# Slave4.net
KiCad netlist of a schematic drawn in Altium Designer
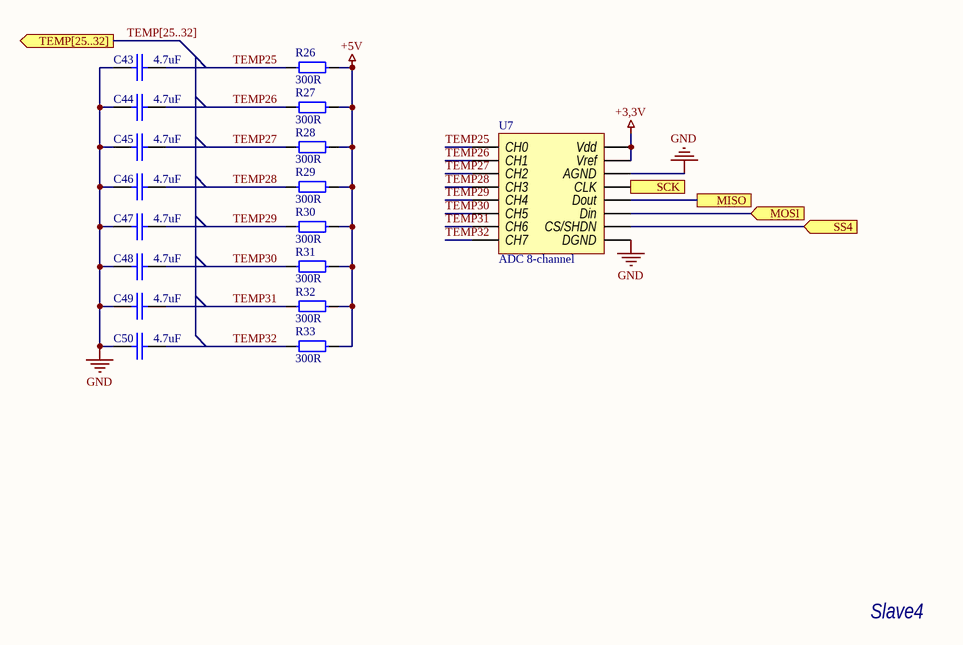
[diagram p0: Slave4.SchDoc]

(export (version "E")
  (design (tool "Eeschema 10.0.6"))
  (components
    (comp (ref "C43")
      (value "4.7uF")
      (footprint "0603 Capicator")
      (description "4.7uF X5R 25V 10% 0603")
      (fields
        (field (name "MANUFACTURER") "Murata Manufacturing")
        (field (name "PART NUMBER") "GRM188R61E475KE11D")
      )
      (libsource (lib "БУС") (part "Cap 4.7uF (0603)"))
    )
    (comp (ref "C44")
      (value "4.7uF")
      (footprint "0603 Capicator")
      (description "4.7uF X5R 25V 10% 0603")
      (fields
        (field (name "MANUFACTURER") "Murata Manufacturing")
        (field (name "PART NUMBER") "GRM188R61E475KE11D")
      )
      (libsource (lib "БУС") (part "Cap 4.7uF (0603)"))
    )
    (comp (ref "C45")
      (value "4.7uF")
      (footprint "0603 Capicator")
      (description "4.7uF X5R 25V 10% 0603")
      (fields
        (field (name "MANUFACTURER") "Murata Manufacturing")
        (field (name "PART NUMBER") "GRM188R61E475KE11D")
      )
      (libsource (lib "БУС") (part "Cap 4.7uF (0603)"))
    )
    (comp (ref "C46")
      (value "4.7uF")
      (footprint "0603 Capicator")
      (description "4.7uF X5R 25V 10% 0603")
      (fields
        (field (name "MANUFACTURER") "Murata Manufacturing")
        (field (name "PART NUMBER") "GRM188R61E475KE11D")
      )
      (libsource (lib "БУС") (part "Cap 4.7uF (0603)"))
    )
    (comp (ref "C47")
      (value "4.7uF")
      (footprint "0603 Capicator")
      (description "4.7uF X5R 25V 10% 0603")
      (fields
        (field (name "MANUFACTURER") "Murata Manufacturing")
        (field (name "PART NUMBER") "GRM188R61E475KE11D")
      )
      (libsource (lib "БУС") (part "Cap 4.7uF (0603)"))
    )
    (comp (ref "C48")
      (value "4.7uF")
      (footprint "0603 Capicator")
      (description "4.7uF X5R 25V 10% 0603")
      (fields
        (field (name "MANUFACTURER") "Murata Manufacturing")
        (field (name "PART NUMBER") "GRM188R61E475KE11D")
      )
      (libsource (lib "БУС") (part "Cap 4.7uF (0603)"))
    )
    (comp (ref "C49")
      (value "4.7uF")
      (footprint "0603 Capicator")
      (description "4.7uF X5R 25V 10% 0603")
      (fields
        (field (name "MANUFACTURER") "Murata Manufacturing")
        (field (name "PART NUMBER") "GRM188R61E475KE11D")
      )
      (libsource (lib "БУС") (part "Cap 4.7uF (0603)"))
    )
    (comp (ref "C50")
      (value "4.7uF")
      (footprint "0603 Capicator")
      (description "4.7uF X5R 25V 10% 0603")
      (fields
        (field (name "MANUFACTURER") "Murata Manufacturing")
        (field (name "PART NUMBER") "GRM188R61E475KE11D")
      )
      (libsource (lib "БУС") (part "Cap 4.7uF (0603)"))
    )
    (comp (ref "R26")
      (value "300R")
      (footprint "0603 Resistor")
      (description "0.1W 0603 300R, 1%")
      (fields (field (name "PART NUMBER") "RC0603FR-07360RL") (field (name "MANUFACTURER") "Taiwan"))
      (libsource (lib "БУС") (part "Res 300R (0603)"))
    )
    (comp (ref "R27")
      (value "300R")
      (footprint "0603 Resistor")
      (description "0.1W 0603 300R, 1%")
      (fields (field (name "PART NUMBER") "RC0603FR-07360RL") (field (name "MANUFACTURER") "Taiwan"))
      (libsource (lib "БУС") (part "Res 300R (0603)"))
    )
    (comp (ref "R28")
      (value "300R")
      (footprint "0603 Resistor")
      (description "0.1W 0603 300R, 1%")
      (fields (field (name "PART NUMBER") "RC0603FR-07360RL") (field (name "MANUFACTURER") "Taiwan"))
      (libsource (lib "БУС") (part "Res 300R (0603)"))
    )
    (comp (ref "R29")
      (value "300R")
      (footprint "0603 Resistor")
      (description "0.1W 0603 300R, 1%")
      (fields (field (name "PART NUMBER") "RC0603FR-07360RL") (field (name "MANUFACTURER") "Taiwan"))
      (libsource (lib "БУС") (part "Res 300R (0603)"))
    )
    (comp (ref "R30")
      (value "300R")
      (footprint "0603 Resistor")
      (description "0.1W 0603 300R, 1%")
      (fields (field (name "PART NUMBER") "RC0603FR-07360RL") (field (name "MANUFACTURER") "Taiwan"))
      (libsource (lib "БУС") (part "Res 300R (0603)"))
    )
    (comp (ref "R31")
      (value "300R")
      (footprint "0603 Resistor")
      (description "0.1W 0603 300R, 1%")
      (fields (field (name "PART NUMBER") "RC0603FR-07360RL") (field (name "MANUFACTURER") "Taiwan"))
      (libsource (lib "БУС") (part "Res 300R (0603)"))
    )
    (comp (ref "R32")
      (value "300R")
      (footprint "0603 Resistor")
      (description "0.1W 0603 300R, 1%")
      (fields (field (name "PART NUMBER") "RC0603FR-07360RL") (field (name "MANUFACTURER") "Taiwan"))
      (libsource (lib "БУС") (part "Res 300R (0603)"))
    )
    (comp (ref "R33")
      (value "300R")
      (footprint "0603 Resistor")
      (description "0.1W 0603 300R, 1%")
      (fields (field (name "PART NUMBER") "RC0603FR-07360RL") (field (name "MANUFACTURER") "Taiwan"))
      (libsource (lib "БУС") (part "Res 300R (0603)"))
    )
    (comp (ref "U7")
      (value "ADC 8-channel")
      (footprint "SOIC-16")
      (description "A/D converter with SPI serial interface")
      (fields (field (name "MANUFACTURER") "Microchip") (field (name "PART NUMBER") "MCP3008-I/SL"))
      (libsource (lib "БУС") (part "MCP3008-I/SL"))
    )
  )
  (nets
    (net (code "1") (name "+3,3V") (class "Default")
      (node (ref "U7") (pin "15") (pinfunction "Vref_15") (pintype "passive"))
      (node (ref "U7") (pin "16") (pinfunction "Vdd_16") (pintype "passive"))
    )
    (net (code "2") (name "+5V") (class "Default")
      (node (ref "R26") (pin "2") (pinfunction "2_2") (pintype "passive"))
      (node (ref "R27") (pin "2") (pinfunction "2_2") (pintype "passive"))
      (node (ref "R28") (pin "2") (pinfunction "2_2") (pintype "passive"))
      (node (ref "R29") (pin "2") (pinfunction "2_2") (pintype "passive"))
      (node (ref "R30") (pin "2") (pinfunction "2_2") (pintype "passive"))
      (node (ref "R31") (pin "2") (pinfunction "2_2") (pintype "passive"))
      (node (ref "R32") (pin "2") (pinfunction "2_2") (pintype "passive"))
      (node (ref "R33") (pin "2") (pinfunction "2_2") (pintype "passive"))
    )
    (net (code "3") (name "/MISO") (class "Default")
      (node (ref "U7") (pin "12") (pinfunction "Dout_12") (pintype "passive"))
    )
    (net (code "4") (name "/MOSI") (class "Default")
      (node (ref "U7") (pin "11") (pinfunction "Din_11") (pintype "passive"))
    )
    (net (code "5") (name "/SCK") (class "Default")
      (node (ref "U7") (pin "13") (pinfunction "CLK_13") (pintype "passive"))
    )
    (net (code "6") (name "/SS4") (class "Default")
      (node (ref "U7") (pin "10") (pinfunction "CS/SHDN_10") (pintype "passive"))
    )
    (net (code "7") (name "/TEMP25") (class "Default")
      (node (ref "C43") (pin "2") (pinfunction "2_2") (pintype "passive"))
      (node (ref "R26") (pin "1") (pinfunction "1_1") (pintype "passive"))
      (node (ref "U7") (pin "1") (pinfunction "CH0_1") (pintype "passive"))
    )
    (net (code "8") (name "/TEMP26") (class "Default")
      (node (ref "C44") (pin "2") (pinfunction "2_2") (pintype "passive"))
      (node (ref "R27") (pin "1") (pinfunction "1_1") (pintype "passive"))
      (node (ref "U7") (pin "2") (pinfunction "CH1_2") (pintype "passive"))
    )
    (net (code "9") (name "/TEMP27") (class "Default")
      (node (ref "C45") (pin "2") (pinfunction "2_2") (pintype "passive"))
      (node (ref "R28") (pin "1") (pinfunction "1_1") (pintype "passive"))
      (node (ref "U7") (pin "3") (pinfunction "CH2_3") (pintype "passive"))
    )
    (net (code "10") (name "/TEMP28") (class "Default")
      (node (ref "C46") (pin "2") (pinfunction "2_2") (pintype "passive"))
      (node (ref "R29") (pin "1") (pinfunction "1_1") (pintype "passive"))
      (node (ref "U7") (pin "4") (pinfunction "CH3_4") (pintype "passive"))
    )
    (net (code "11") (name "/TEMP29") (class "Default")
      (node (ref "C47") (pin "2") (pinfunction "2_2") (pintype "passive"))
      (node (ref "R30") (pin "1") (pinfunction "1_1") (pintype "passive"))
      (node (ref "U7") (pin "5") (pinfunction "CH4_5") (pintype "passive"))
    )
    (net (code "12") (name "/TEMP30") (class "Default")
      (node (ref "C48") (pin "2") (pinfunction "2_2") (pintype "passive"))
      (node (ref "R31") (pin "1") (pinfunction "1_1") (pintype "passive"))
      (node (ref "U7") (pin "6") (pinfunction "CH5_6") (pintype "passive"))
    )
    (net (code "13") (name "/TEMP31") (class "Default")
      (node (ref "C49") (pin "2") (pinfunction "2_2") (pintype "passive"))
      (node (ref "R32") (pin "1") (pinfunction "1_1") (pintype "passive"))
      (node (ref "U7") (pin "7") (pinfunction "CH6_7") (pintype "passive"))
    )
    (net (code "14") (name "/TEMP32") (class "Default")
      (node (ref "C50") (pin "2") (pinfunction "2_2") (pintype "passive"))
      (node (ref "R33") (pin "1") (pinfunction "1_1") (pintype "passive"))
      (node (ref "U7") (pin "8") (pinfunction "CH7_8") (pintype "passive"))
    )
    (net (code "16") (name "GND") (class "Default")
      (node (ref "C43") (pin "1") (pinfunction "1_1") (pintype "passive"))
      (node (ref "C44") (pin "1") (pinfunction "1_1") (pintype "passive"))
      (node (ref "C45") (pin "1") (pinfunction "1_1") (pintype "passive"))
      (node (ref "C46") (pin "1") (pinfunction "1_1") (pintype "passive"))
      (node (ref "C47") (pin "1") (pinfunction "1_1") (pintype "passive"))
      (node (ref "C48") (pin "1") (pinfunction "1_1") (pintype "passive"))
      (node (ref "C49") (pin "1") (pinfunction "1_1") (pintype "passive"))
      (node (ref "C50") (pin "1") (pinfunction "1_1") (pintype "passive"))
      (node (ref "U7") (pin "14") (pinfunction "AGND_14") (pintype "passive"))
      (node (ref "U7") (pin "9") (pinfunction "DGND_9") (pintype "passive"))
    )
  )
)
